# untitled.net
KiCad netlist of a schematic drawn in EAGLE
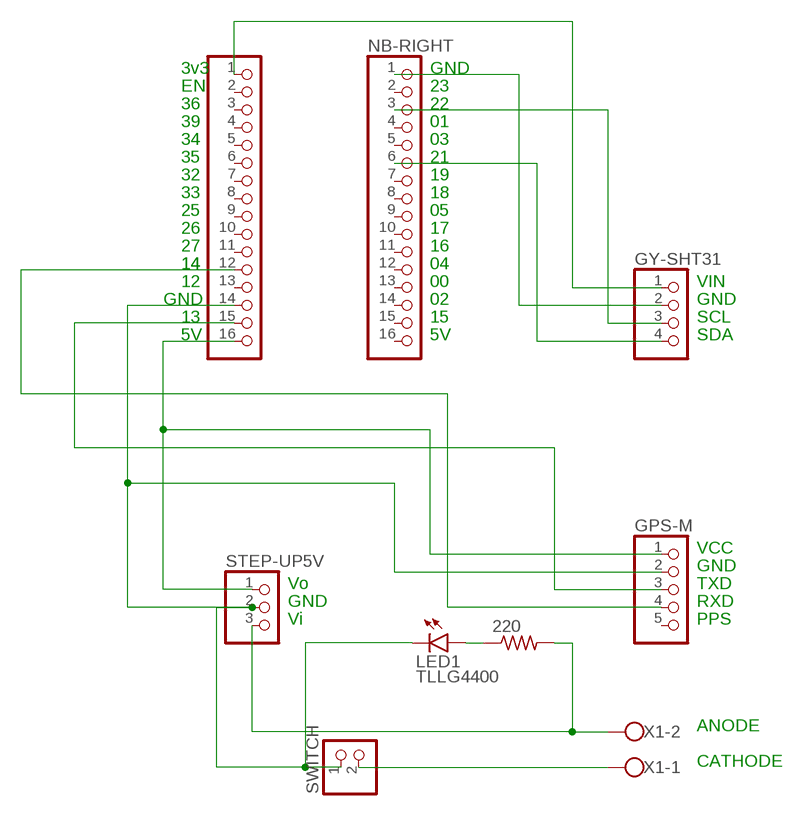
[diagram p0: schematic, sheet 1]

(export (version "E")
  (design (tool "Eeschema 10.0.6"))
  (components
    (comp (ref "220")
      (value "R-US_0204/7")
      (footprint "eagle-import:0204_7")
      (libsource (lib "eagle-import") (part "R-US_0204/7"))
    )
    (comp (ref "GPS-M")
      (value "PINHD-1X5")
      (footprint "eagle-import:1X05")
      (libsource (lib "eagle-import") (part "PINHD-1X5"))
    )
    (comp (ref "GY-SHT31")
      (value "PINHD-1X4")
      (footprint "eagle-import:1X04")
      (libsource (lib "eagle-import") (part "PINHD-1X4"))
    )
    (comp (ref "LED1")
      (value "TLLG4400")
      (footprint "eagle-import:LED3MM")
      (fields (field (name "MF") "VISHAY SEMICONDUCTOR"))
      (libsource (lib "eagle-import") (part "TLLG4400"))
    )
    (comp (ref "NB-LEFT")
      (value "PINHD-1X16")
      (footprint "eagle-import:1X16")
      (libsource (lib "eagle-import") (part "PINHD-1X16"))
    )
    (comp (ref "NB-RIGHT")
      (value "PINHD-1X16")
      (footprint "eagle-import:1X16")
      (libsource (lib "eagle-import") (part "PINHD-1X16"))
    )
    (comp (ref "STEP-UP5V")
      (value "PINHD-1X3")
      (footprint "eagle-import:1X03")
      (libsource (lib "eagle-import") (part "PINHD-1X3"))
    )
    (comp (ref "SWITCH")
      (value "PINHD-1X2")
      (footprint "eagle-import:1X02")
      (libsource (lib "eagle-import") (part "PINHD-1X2"))
    )
    (comp (ref "X1")
      (value "W237-102")
      (footprint "eagle-import:W237-102")
      (fields (field (name "MPN") "237-102"))
      (libsource (lib "eagle-import") (part "W237-102"))
    )
  )
  (nets
    (net (code "1") (name "Net-(220-Pad1)") (class "Default")
      (node (ref "220") (pin "1") (pinfunction "1_1") (pintype "passive"))
      (node (ref "LED1") (pin "A") (pinfunction "A_A") (pintype "passive"))
    )
    (net (code "2") (name "Net-(GPS-M-Pad1)") (class "Default")
      (node (ref "GPS-M") (pin "1") (pinfunction "1_1") (pintype "passive"))
      (node (ref "NB-LEFT") (pin "16") (pinfunction "16_16") (pintype "passive"))
      (node (ref "STEP-UP5V") (pin "1") (pinfunction "1_1") (pintype "passive"))
    )
    (net (code "3") (name "Net-(GPS-M-Pad3)") (class "Default")
      (node (ref "GPS-M") (pin "3") (pinfunction "3_3") (pintype "passive"))
      (node (ref "NB-LEFT") (pin "15") (pinfunction "15_15") (pintype "passive"))
    )
    (net (code "4") (name "Net-(GPS-M-Pad4)") (class "Default")
      (node (ref "GPS-M") (pin "4") (pinfunction "4_4") (pintype "passive"))
      (node (ref "NB-LEFT") (pin "12") (pinfunction "12_12") (pintype "passive"))
    )
    (net (code "5") (name "Net-(GY-SHT31-Pad1)") (class "Default")
      (node (ref "GY-SHT31") (pin "1") (pinfunction "1_1") (pintype "passive"))
      (node (ref "NB-LEFT") (pin "1") (pinfunction "1_1") (pintype "passive"))
    )
    (net (code "6") (name "Net-(GY-SHT31-Pad2)") (class "Default")
      (node (ref "GY-SHT31") (pin "2") (pinfunction "2_2") (pintype "passive"))
      (node (ref "NB-RIGHT") (pin "1") (pinfunction "1_1") (pintype "passive"))
    )
    (net (code "7") (name "Net-(GY-SHT31-Pad3)") (class "Default")
      (node (ref "GY-SHT31") (pin "3") (pinfunction "3_3") (pintype "passive"))
      (node (ref "NB-RIGHT") (pin "3") (pinfunction "3_3") (pintype "passive"))
    )
    (net (code "8") (name "Net-(GY-SHT31-Pad4)") (class "Default")
      (node (ref "GY-SHT31") (pin "4") (pinfunction "4_4") (pintype "passive"))
      (node (ref "NB-RIGHT") (pin "6") (pinfunction "6_6") (pintype "passive"))
    )
    (net (code "9") (name "Net-(LED1-C)") (class "Default")
      (node (ref "GPS-M") (pin "2") (pinfunction "2_2") (pintype "passive"))
      (node (ref "LED1") (pin "K") (pinfunction "C_K") (pintype "passive"))
      (node (ref "NB-LEFT") (pin "14") (pinfunction "14_14") (pintype "passive"))
      (node (ref "STEP-UP5V") (pin "2") (pinfunction "2_2") (pintype "passive"))
      (node (ref "SWITCH") (pin "1") (pinfunction "1_1") (pintype "passive"))
    )
    (net (code "10") (name "Net-(X1A-KL)") (class "Default")
      (node (ref "SWITCH") (pin "2") (pinfunction "2_2") (pintype "passive"))
      (node (ref "X1") (pin "1") (pinfunction "KL_1") (pintype "passive"))
    )
    (net (code "11") (name "Net-(X1B-KL)") (class "Default")
      (node (ref "220") (pin "2") (pinfunction "2_2") (pintype "passive"))
      (node (ref "STEP-UP5V") (pin "3") (pinfunction "3_3") (pintype "passive"))
      (node (ref "X1") (pin "2") (pinfunction "KL_2") (pintype "passive"))
    )
    (net (code "12") (name "unconnected-(GPS-M-Pad5)") (class "Default")
      (node (ref "GPS-M") (pin "5") (pinfunction "5_5") (pintype "passive"))
    )
    (net (code "13") (name "unconnected-(NB-LEFT-Pad2)") (class "Default")
      (node (ref "NB-LEFT") (pin "2") (pinfunction "2_2") (pintype "passive"))
    )
    (net (code "14") (name "unconnected-(NB-LEFT-Pad3)") (class "Default")
      (node (ref "NB-LEFT") (pin "3") (pinfunction "3_3") (pintype "passive"))
    )
    (net (code "15") (name "unconnected-(NB-LEFT-Pad4)") (class "Default")
      (node (ref "NB-LEFT") (pin "4") (pinfunction "4_4") (pintype "passive"))
    )
    (net (code "16") (name "unconnected-(NB-LEFT-Pad5)") (class "Default")
      (node (ref "NB-LEFT") (pin "5") (pinfunction "5_5") (pintype "passive"))
    )
    (net (code "17") (name "unconnected-(NB-LEFT-Pad6)") (class "Default")
      (node (ref "NB-LEFT") (pin "6") (pinfunction "6_6") (pintype "passive"))
    )
    (net (code "18") (name "unconnected-(NB-LEFT-Pad7)") (class "Default")
      (node (ref "NB-LEFT") (pin "7") (pinfunction "7_7") (pintype "passive"))
    )
    (net (code "19") (name "unconnected-(NB-LEFT-Pad8)") (class "Default")
      (node (ref "NB-LEFT") (pin "8") (pinfunction "8_8") (pintype "passive"))
    )
    (net (code "20") (name "unconnected-(NB-LEFT-Pad9)") (class "Default")
      (node (ref "NB-LEFT") (pin "9") (pinfunction "9_9") (pintype "passive"))
    )
    (net (code "21") (name "unconnected-(NB-LEFT-Pad10)") (class "Default")
      (node (ref "NB-LEFT") (pin "10") (pinfunction "10_10") (pintype "passive"))
    )
    (net (code "22") (name "unconnected-(NB-LEFT-Pad11)") (class "Default")
      (node (ref "NB-LEFT") (pin "11") (pinfunction "11_11") (pintype "passive"))
    )
    (net (code "23") (name "unconnected-(NB-LEFT-Pad13)") (class "Default")
      (node (ref "NB-LEFT") (pin "13") (pinfunction "13_13") (pintype "passive"))
    )
    (net (code "24") (name "unconnected-(NB-RIGHT-Pad2)") (class "Default")
      (node (ref "NB-RIGHT") (pin "2") (pinfunction "2_2") (pintype "passive"))
    )
    (net (code "25") (name "unconnected-(NB-RIGHT-Pad4)") (class "Default")
      (node (ref "NB-RIGHT") (pin "4") (pinfunction "4_4") (pintype "passive"))
    )
    (net (code "26") (name "unconnected-(NB-RIGHT-Pad5)") (class "Default")
      (node (ref "NB-RIGHT") (pin "5") (pinfunction "5_5") (pintype "passive"))
    )
    (net (code "27") (name "unconnected-(NB-RIGHT-Pad7)") (class "Default")
      (node (ref "NB-RIGHT") (pin "7") (pinfunction "7_7") (pintype "passive"))
    )
    (net (code "28") (name "unconnected-(NB-RIGHT-Pad8)") (class "Default")
      (node (ref "NB-RIGHT") (pin "8") (pinfunction "8_8") (pintype "passive"))
    )
    (net (code "29") (name "unconnected-(NB-RIGHT-Pad9)") (class "Default")
      (node (ref "NB-RIGHT") (pin "9") (pinfunction "9_9") (pintype "passive"))
    )
    (net (code "30") (name "unconnected-(NB-RIGHT-Pad10)") (class "Default")
      (node (ref "NB-RIGHT") (pin "10") (pinfunction "10_10") (pintype "passive"))
    )
    (net (code "31") (name "unconnected-(NB-RIGHT-Pad11)") (class "Default")
      (node (ref "NB-RIGHT") (pin "11") (pinfunction "11_11") (pintype "passive"))
    )
    (net (code "32") (name "unconnected-(NB-RIGHT-Pad12)") (class "Default")
      (node (ref "NB-RIGHT") (pin "12") (pinfunction "12_12") (pintype "passive"))
    )
    (net (code "33") (name "unconnected-(NB-RIGHT-Pad13)") (class "Default")
      (node (ref "NB-RIGHT") (pin "13") (pinfunction "13_13") (pintype "passive"))
    )
    (net (code "34") (name "unconnected-(NB-RIGHT-Pad14)") (class "Default")
      (node (ref "NB-RIGHT") (pin "14") (pinfunction "14_14") (pintype "passive"))
    )
    (net (code "35") (name "unconnected-(NB-RIGHT-Pad15)") (class "Default")
      (node (ref "NB-RIGHT") (pin "15") (pinfunction "15_15") (pintype "passive"))
    )
    (net (code "36") (name "unconnected-(NB-RIGHT-Pad16)") (class "Default")
      (node (ref "NB-RIGHT") (pin "16") (pinfunction "16_16") (pintype "passive"))
    )
  )
)
